# power_injector_rev_c.net
KiCad netlist of a schematic drawn in EAGLE
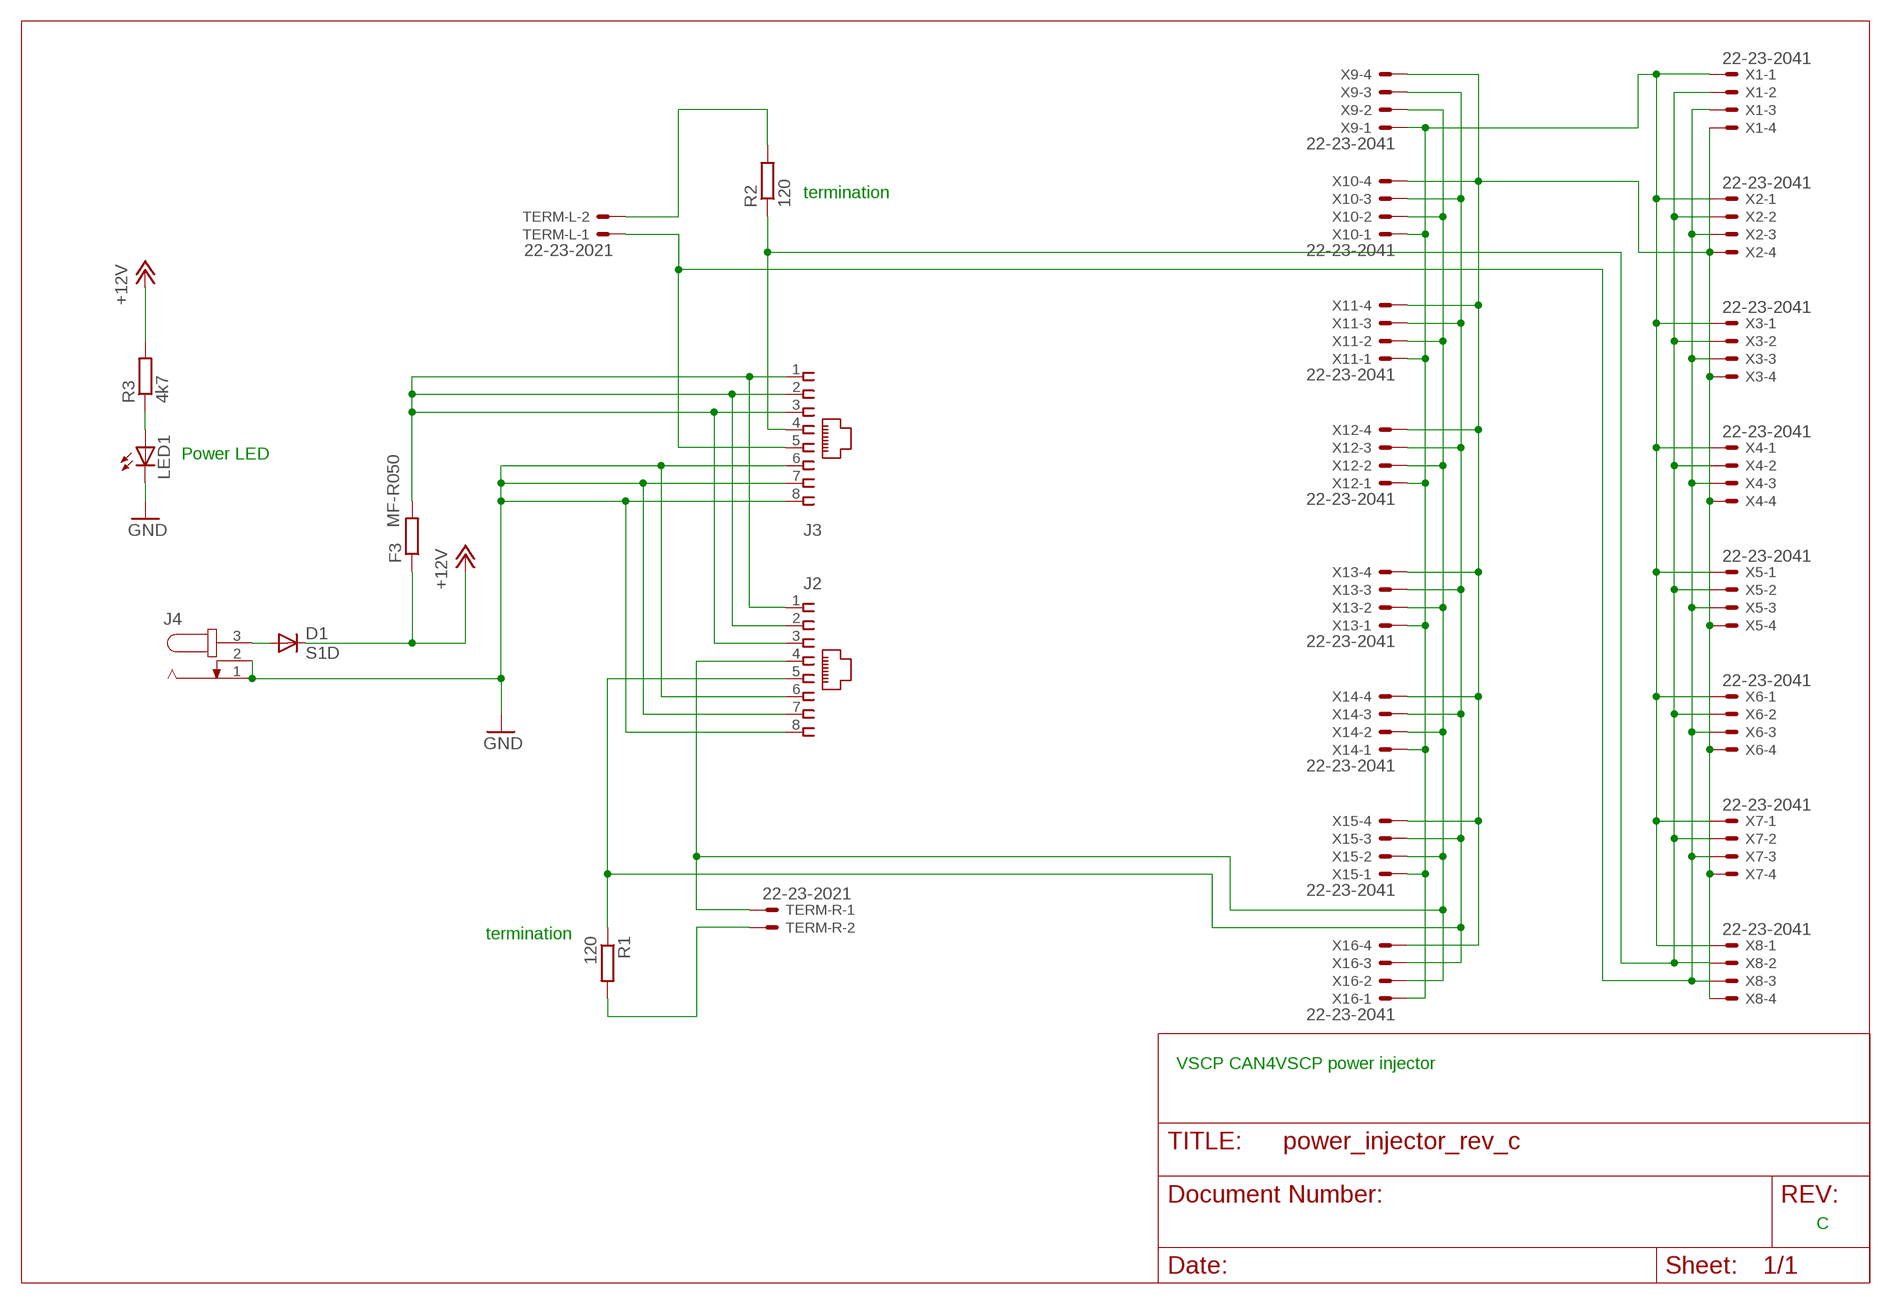
[diagram p0: schematic, sheet 1]

(export (version "E")
  (design (tool "Eeschema 10.0.6"))
  (components
    (comp (ref "D1")
      (value "S1D")
      (footprint "eagle-import:SMB")
      (libsource (lib "eagle-import") (part "DIODE-SMB"))
    )
    (comp (ref "F3")
      (value "MF-R050")
      (footprint "eagle-import:0204_5")
      (libsource (lib "eagle-import") (part "R-EU_0204/5"))
    )
    (comp (ref "J2")
      (value "A00-108-220-450")
      (footprint "eagle-import:RJ-45")
      (libsource (lib "eagle-import") (part "A00-108-220-450"))
    )
    (comp (ref "J3")
      (value "A00-108-220-450")
      (footprint "eagle-import:RJ-45")
      (libsource (lib "eagle-import") (part "A00-108-220-450"))
    )
    (comp (ref "J4")
      (value "JACK-PLUG0")
      (footprint "eagle-import:SPC4077")
      (libsource (lib "eagle-import") (part "JACK-PLUG0"))
    )
    (comp (ref "LED1")
      (value "LEDCHIP-LED0805")
      (footprint "eagle-import:CHIP-LED0805")
      (libsource (lib "eagle-import") (part "LEDCHIP-LED0805"))
    )
    (comp (ref "R1")
      (value "120")
      (footprint "eagle-import:R0805")
      (libsource (lib "eagle-import") (part "R-EU_R0805"))
    )
    (comp (ref "R2")
      (value "120")
      (footprint "eagle-import:R0805")
      (libsource (lib "eagle-import") (part "R-EU_R0805"))
    )
    (comp (ref "R3")
      (value "4k7")
      (footprint "eagle-import:R0805")
      (libsource (lib "eagle-import") (part "R-EU_R0805"))
    )
    (comp (ref "TERM-L")
      (value "22-23-2021")
      (footprint "eagle-import:22-23-2021")
      (fields (field (name "MF") "MOLEX"))
      (libsource (lib "eagle-import") (part "22-23-2021"))
    )
    (comp (ref "TERM-R")
      (value "22-23-2021")
      (footprint "eagle-import:22-23-2021")
      (fields (field (name "MF") "MOLEX"))
      (libsource (lib "eagle-import") (part "22-23-2021"))
    )
    (comp (ref "X1")
      (value "22-23-2041")
      (footprint "eagle-import:22-23-2041")
      (fields (field (name "MF") "MOLEX"))
      (libsource (lib "eagle-import") (part "22-23-2041"))
    )
    (comp (ref "X2")
      (value "22-23-2041")
      (footprint "eagle-import:22-23-2041")
      (fields (field (name "MF") "MOLEX"))
      (libsource (lib "eagle-import") (part "22-23-2041"))
    )
    (comp (ref "X3")
      (value "22-23-2041")
      (footprint "eagle-import:22-23-2041")
      (fields (field (name "MF") "MOLEX"))
      (libsource (lib "eagle-import") (part "22-23-2041"))
    )
    (comp (ref "X4")
      (value "22-23-2041")
      (footprint "eagle-import:22-23-2041")
      (fields (field (name "MF") "MOLEX"))
      (libsource (lib "eagle-import") (part "22-23-2041"))
    )
    (comp (ref "X5")
      (value "22-23-2041")
      (footprint "eagle-import:22-23-2041")
      (fields (field (name "MF") "MOLEX"))
      (libsource (lib "eagle-import") (part "22-23-2041"))
    )
    (comp (ref "X6")
      (value "22-23-2041")
      (footprint "eagle-import:22-23-2041")
      (fields (field (name "MF") "MOLEX"))
      (libsource (lib "eagle-import") (part "22-23-2041"))
    )
    (comp (ref "X7")
      (value "22-23-2041")
      (footprint "eagle-import:22-23-2041")
      (fields (field (name "MF") "MOLEX"))
      (libsource (lib "eagle-import") (part "22-23-2041"))
    )
    (comp (ref "X8")
      (value "22-23-2041")
      (footprint "eagle-import:22-23-2041")
      (fields (field (name "MF") "MOLEX"))
      (libsource (lib "eagle-import") (part "22-23-2041"))
    )
    (comp (ref "X9")
      (value "22-23-2041")
      (footprint "eagle-import:22-23-2041")
      (fields (field (name "MF") "MOLEX"))
      (libsource (lib "eagle-import") (part "22-23-2041"))
    )
    (comp (ref "X10")
      (value "22-23-2041")
      (footprint "eagle-import:22-23-2041")
      (fields (field (name "MF") "MOLEX"))
      (libsource (lib "eagle-import") (part "22-23-2041"))
    )
    (comp (ref "X11")
      (value "22-23-2041")
      (footprint "eagle-import:22-23-2041")
      (fields (field (name "MF") "MOLEX"))
      (libsource (lib "eagle-import") (part "22-23-2041"))
    )
    (comp (ref "X12")
      (value "22-23-2041")
      (footprint "eagle-import:22-23-2041")
      (fields (field (name "MF") "MOLEX"))
      (libsource (lib "eagle-import") (part "22-23-2041"))
    )
    (comp (ref "X13")
      (value "22-23-2041")
      (footprint "eagle-import:22-23-2041")
      (fields (field (name "MF") "MOLEX"))
      (libsource (lib "eagle-import") (part "22-23-2041"))
    )
    (comp (ref "X14")
      (value "22-23-2041")
      (footprint "eagle-import:22-23-2041")
      (fields (field (name "MF") "MOLEX"))
      (libsource (lib "eagle-import") (part "22-23-2041"))
    )
    (comp (ref "X15")
      (value "22-23-2041")
      (footprint "eagle-import:22-23-2041")
      (fields (field (name "MF") "MOLEX"))
      (libsource (lib "eagle-import") (part "22-23-2041"))
    )
    (comp (ref "X16")
      (value "22-23-2041")
      (footprint "eagle-import:22-23-2041")
      (fields (field (name "MF") "MOLEX"))
      (libsource (lib "eagle-import") (part "22-23-2041"))
    )
  )
  (nets
    (net (code "1") (name "+12V") (class "Default")
      (node (ref "D1") (pin "C") (pinfunction "C_C") (pintype "passive"))
      (node (ref "F3") (pin "1") (pinfunction "1_1") (pintype "passive"))
      (node (ref "R3") (pin "2") (pinfunction "2_2") (pintype "passive"))
    )
    (net (code "2") (name "/CANH") (class "Default")
      (node (ref "J2") (pin "4") (pinfunction "4_4") (pintype "passive"))
      (node (ref "J3") (pin "4") (pinfunction "4_4") (pintype "passive"))
      (node (ref "R2") (pin "1") (pinfunction "1_1") (pintype "passive"))
      (node (ref "TERM-R") (pin "1") (pinfunction "S_1") (pintype "passive"))
      (node (ref "X1") (pin "2") (pinfunction "S_2") (pintype "passive"))
      (node (ref "X10") (pin "2") (pinfunction "S_2") (pintype "passive"))
      (node (ref "X11") (pin "2") (pinfunction "S_2") (pintype "passive"))
      (node (ref "X12") (pin "2") (pinfunction "S_2") (pintype "passive"))
      (node (ref "X13") (pin "2") (pinfunction "S_2") (pintype "passive"))
      (node (ref "X14") (pin "2") (pinfunction "S_2") (pintype "passive"))
      (node (ref "X15") (pin "2") (pinfunction "S_2") (pintype "passive"))
      (node (ref "X16") (pin "2") (pinfunction "S_2") (pintype "passive"))
      (node (ref "X2") (pin "2") (pinfunction "S_2") (pintype "passive"))
      (node (ref "X3") (pin "2") (pinfunction "S_2") (pintype "passive"))
      (node (ref "X4") (pin "2") (pinfunction "S_2") (pintype "passive"))
      (node (ref "X5") (pin "2") (pinfunction "S_2") (pintype "passive"))
      (node (ref "X6") (pin "2") (pinfunction "S_2") (pintype "passive"))
      (node (ref "X7") (pin "2") (pinfunction "S_2") (pintype "passive"))
      (node (ref "X8") (pin "2") (pinfunction "S_2") (pintype "passive"))
      (node (ref "X9") (pin "2") (pinfunction "S_2") (pintype "passive"))
    )
    (net (code "3") (name "/CANL") (class "Default")
      (node (ref "J2") (pin "5") (pinfunction "5_5") (pintype "passive"))
      (node (ref "J3") (pin "5") (pinfunction "5_5") (pintype "passive"))
      (node (ref "R1") (pin "1") (pinfunction "1_1") (pintype "passive"))
      (node (ref "TERM-L") (pin "1") (pinfunction "S_1") (pintype "passive"))
      (node (ref "X1") (pin "3") (pinfunction "S_3") (pintype "passive"))
      (node (ref "X10") (pin "3") (pinfunction "S_3") (pintype "passive"))
      (node (ref "X11") (pin "3") (pinfunction "S_3") (pintype "passive"))
      (node (ref "X12") (pin "3") (pinfunction "S_3") (pintype "passive"))
      (node (ref "X13") (pin "3") (pinfunction "S_3") (pintype "passive"))
      (node (ref "X14") (pin "3") (pinfunction "S_3") (pintype "passive"))
      (node (ref "X15") (pin "3") (pinfunction "S_3") (pintype "passive"))
      (node (ref "X16") (pin "3") (pinfunction "S_3") (pintype "passive"))
      (node (ref "X2") (pin "3") (pinfunction "S_3") (pintype "passive"))
      (node (ref "X3") (pin "3") (pinfunction "S_3") (pintype "passive"))
      (node (ref "X4") (pin "3") (pinfunction "S_3") (pintype "passive"))
      (node (ref "X5") (pin "3") (pinfunction "S_3") (pintype "passive"))
      (node (ref "X6") (pin "3") (pinfunction "S_3") (pintype "passive"))
      (node (ref "X7") (pin "3") (pinfunction "S_3") (pintype "passive"))
      (node (ref "X8") (pin "3") (pinfunction "S_3") (pintype "passive"))
      (node (ref "X9") (pin "3") (pinfunction "S_3") (pintype "passive"))
    )
    (net (code "4") (name "/POWER") (class "Default")
      (node (ref "F3") (pin "2") (pinfunction "2_2") (pintype "passive"))
      (node (ref "J2") (pin "1") (pinfunction "1_1") (pintype "passive"))
      (node (ref "J2") (pin "2") (pinfunction "2_2") (pintype "passive"))
      (node (ref "J2") (pin "3") (pinfunction "3_3") (pintype "passive"))
      (node (ref "J3") (pin "1") (pinfunction "1_1") (pintype "passive"))
      (node (ref "J3") (pin "2") (pinfunction "2_2") (pintype "passive"))
      (node (ref "J3") (pin "3") (pinfunction "3_3") (pintype "passive"))
      (node (ref "X1") (pin "1") (pinfunction "S_1") (pintype "passive"))
      (node (ref "X10") (pin "1") (pinfunction "S_1") (pintype "passive"))
      (node (ref "X11") (pin "1") (pinfunction "S_1") (pintype "passive"))
      (node (ref "X12") (pin "1") (pinfunction "S_1") (pintype "passive"))
      (node (ref "X13") (pin "1") (pinfunction "S_1") (pintype "passive"))
      (node (ref "X14") (pin "1") (pinfunction "S_1") (pintype "passive"))
      (node (ref "X15") (pin "1") (pinfunction "S_1") (pintype "passive"))
      (node (ref "X16") (pin "1") (pinfunction "S_1") (pintype "passive"))
      (node (ref "X2") (pin "1") (pinfunction "S_1") (pintype "passive"))
      (node (ref "X3") (pin "1") (pinfunction "S_1") (pintype "passive"))
      (node (ref "X4") (pin "1") (pinfunction "S_1") (pintype "passive"))
      (node (ref "X5") (pin "1") (pinfunction "S_1") (pintype "passive"))
      (node (ref "X6") (pin "1") (pinfunction "S_1") (pintype "passive"))
      (node (ref "X7") (pin "1") (pinfunction "S_1") (pintype "passive"))
      (node (ref "X8") (pin "1") (pinfunction "S_1") (pintype "passive"))
      (node (ref "X9") (pin "1") (pinfunction "S_1") (pintype "passive"))
    )
    (net (code "5") (name "GND") (class "Default")
      (node (ref "J2") (pin "6") (pinfunction "6_6") (pintype "passive"))
      (node (ref "J2") (pin "7") (pinfunction "7_7") (pintype "passive"))
      (node (ref "J2") (pin "8") (pinfunction "8_8") (pintype "passive"))
      (node (ref "J3") (pin "6") (pinfunction "6_6") (pintype "passive"))
      (node (ref "J3") (pin "7") (pinfunction "7_7") (pintype "passive"))
      (node (ref "J3") (pin "8") (pinfunction "8_8") (pintype "passive"))
      (node (ref "J4") (pin "1") (pinfunction "1_1") (pintype "passive"))
      (node (ref "J4") (pin "2") (pinfunction "2_2") (pintype "passive"))
      (node (ref "LED1") (pin "C") (pinfunction "C_C") (pintype "passive"))
      (node (ref "X1") (pin "4") (pinfunction "S_4") (pintype "passive"))
      (node (ref "X10") (pin "4") (pinfunction "S_4") (pintype "passive"))
      (node (ref "X11") (pin "4") (pinfunction "S_4") (pintype "passive"))
      (node (ref "X12") (pin "4") (pinfunction "S_4") (pintype "passive"))
      (node (ref "X13") (pin "4") (pinfunction "S_4") (pintype "passive"))
      (node (ref "X14") (pin "4") (pinfunction "S_4") (pintype "passive"))
      (node (ref "X15") (pin "4") (pinfunction "S_4") (pintype "passive"))
      (node (ref "X16") (pin "4") (pinfunction "S_4") (pintype "passive"))
      (node (ref "X2") (pin "4") (pinfunction "S_4") (pintype "passive"))
      (node (ref "X3") (pin "4") (pinfunction "S_4") (pintype "passive"))
      (node (ref "X4") (pin "4") (pinfunction "S_4") (pintype "passive"))
      (node (ref "X5") (pin "4") (pinfunction "S_4") (pintype "passive"))
      (node (ref "X6") (pin "4") (pinfunction "S_4") (pintype "passive"))
      (node (ref "X7") (pin "4") (pinfunction "S_4") (pintype "passive"))
      (node (ref "X8") (pin "4") (pinfunction "S_4") (pintype "passive"))
      (node (ref "X9") (pin "4") (pinfunction "S_4") (pintype "passive"))
    )
    (net (code "6") (name "Net-(D1-PadA)") (class "Default")
      (node (ref "D1") (pin "A") (pinfunction "A_A") (pintype "passive"))
      (node (ref "J4") (pin "3") (pinfunction "3_3") (pintype "passive"))
    )
    (net (code "7") (name "Net-(LED1-PadA)") (class "Default")
      (node (ref "LED1") (pin "A") (pinfunction "A_A") (pintype "passive"))
      (node (ref "R3") (pin "1") (pinfunction "1_1") (pintype "passive"))
    )
    (net (code "8") (name "Net-(TERM-LB-S)") (class "Default")
      (node (ref "R2") (pin "2") (pinfunction "2_2") (pintype "passive"))
      (node (ref "TERM-L") (pin "2") (pinfunction "S_2") (pintype "passive"))
    )
    (net (code "9") (name "Net-(TERM-RB-S)") (class "Default")
      (node (ref "R1") (pin "2") (pinfunction "2_2") (pintype "passive"))
      (node (ref "TERM-R") (pin "2") (pinfunction "S_2") (pintype "passive"))
    )
  )
)
